# W960.net
KiCad netlist of a schematic drawn in EAGLE
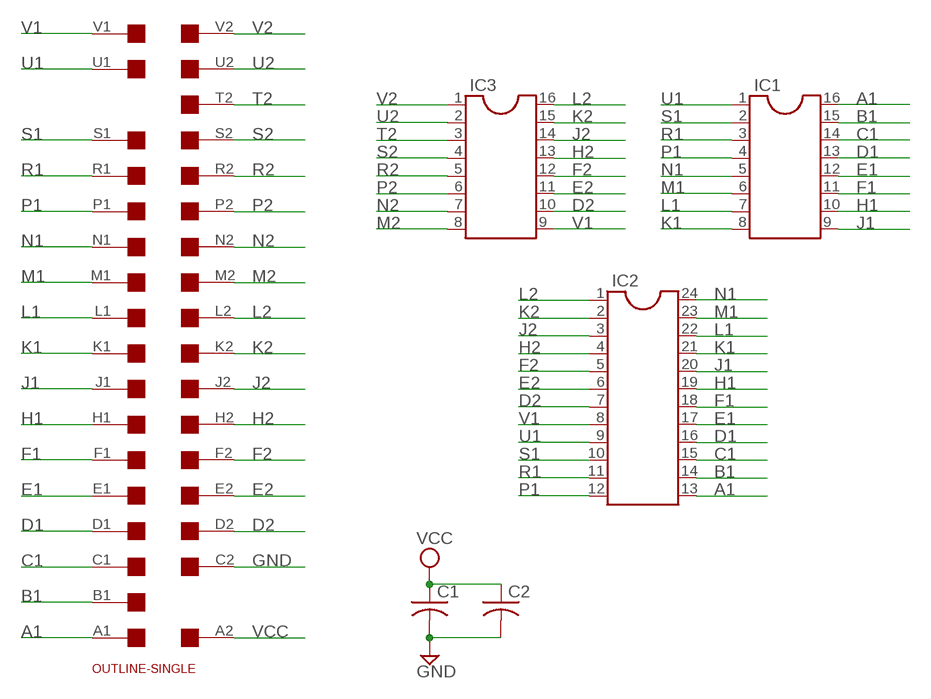
[diagram p0: schematic, sheet 1]

(export (version "E")
  (design (tool "Eeschema 10.0.6"))
  (components
    (comp (ref "C1")
      (value "C-US050-025X075")
      (footprint "eagle-import:C050-025X075")
      (libsource (lib "eagle-import") (part "C-US050-025X075"))
    )
    (comp (ref "C2")
      (value "C-US050-025X075")
      (footprint "eagle-import:C050-025X075")
      (libsource (lib "eagle-import") (part "C-US050-025X075"))
    )
    (comp (ref "IC1")
      (value "DIL16")
      (footprint "eagle-import:DIL16")
      (libsource (lib "eagle-import") (part "DIL16"))
    )
    (comp (ref "IC2")
      (value "DIL24-6")
      (footprint "eagle-import:DIL24-6")
      (libsource (lib "eagle-import") (part "DIL24-6"))
    )
    (comp (ref "IC3")
      (value "DIL16")
      (footprint "eagle-import:DIL16")
      (libsource (lib "eagle-import") (part "DIL16"))
    )
    (comp (ref "U$1")
      (value "EDGE-2CONNECTOR")
      (footprint "eagle-import:EDGE-CON2")
      (libsource (lib "eagle-import") (part "EDGE-2CONNECTOR"))
    )
    (comp (ref "U$2")
      (value "OUTLINE-SINGLE")
      (footprint "eagle-import:SINGLE")
      (libsource (lib "eagle-import") (part "OUTLINE-SINGLE"))
    )
  )
  (nets
    (net (code "1") (name "/A1") (class "Default")
      (node (ref "IC1") (pin "16") (pinfunction "16_16") (pintype "passive"))
      (node (ref "IC2") (pin "13") (pinfunction "13_13") (pintype "passive"))
      (node (ref "U$1") (pin "A1") (pinfunction "1_A1") (pintype "bidirectional"))
    )
    (net (code "2") (name "/B1") (class "Default")
      (node (ref "IC1") (pin "15") (pinfunction "15_15") (pintype "passive"))
      (node (ref "IC2") (pin "14") (pinfunction "14_14") (pintype "passive"))
      (node (ref "U$1") (pin "B1") (pinfunction "1_B1") (pintype "bidirectional"))
    )
    (net (code "3") (name "/C1") (class "Default")
      (node (ref "IC1") (pin "14") (pinfunction "14_14") (pintype "passive"))
      (node (ref "IC2") (pin "15") (pinfunction "15_15") (pintype "passive"))
      (node (ref "U$1") (pin "C1") (pinfunction "1_C1") (pintype "bidirectional"))
    )
    (net (code "4") (name "/D1") (class "Default")
      (node (ref "IC1") (pin "13") (pinfunction "13_13") (pintype "passive"))
      (node (ref "IC2") (pin "16") (pinfunction "16_16") (pintype "passive"))
      (node (ref "U$1") (pin "D1") (pinfunction "1_D1") (pintype "bidirectional"))
    )
    (net (code "5") (name "/D2") (class "Default")
      (node (ref "IC2") (pin "7") (pinfunction "7_7") (pintype "passive"))
      (node (ref "IC3") (pin "10") (pinfunction "10_10") (pintype "passive"))
      (node (ref "U$1") (pin "D2") (pinfunction "1_D2") (pintype "bidirectional"))
    )
    (net (code "6") (name "/E1") (class "Default")
      (node (ref "IC1") (pin "12") (pinfunction "12_12") (pintype "passive"))
      (node (ref "IC2") (pin "17") (pinfunction "17_17") (pintype "passive"))
      (node (ref "U$1") (pin "E1") (pinfunction "1_E1") (pintype "bidirectional"))
    )
    (net (code "7") (name "/E2") (class "Default")
      (node (ref "IC2") (pin "6") (pinfunction "6_6") (pintype "passive"))
      (node (ref "IC3") (pin "11") (pinfunction "11_11") (pintype "passive"))
      (node (ref "U$1") (pin "E2") (pinfunction "1_E2") (pintype "bidirectional"))
    )
    (net (code "8") (name "/F1") (class "Default")
      (node (ref "IC1") (pin "11") (pinfunction "11_11") (pintype "passive"))
      (node (ref "IC2") (pin "18") (pinfunction "18_18") (pintype "passive"))
      (node (ref "U$1") (pin "F1") (pinfunction "1_F1") (pintype "bidirectional"))
    )
    (net (code "9") (name "/F2") (class "Default")
      (node (ref "IC2") (pin "5") (pinfunction "5_5") (pintype "passive"))
      (node (ref "IC3") (pin "12") (pinfunction "12_12") (pintype "passive"))
      (node (ref "U$1") (pin "F2") (pinfunction "1_F2") (pintype "bidirectional"))
    )
    (net (code "10") (name "/H1") (class "Default")
      (node (ref "IC1") (pin "10") (pinfunction "10_10") (pintype "passive"))
      (node (ref "IC2") (pin "19") (pinfunction "19_19") (pintype "passive"))
      (node (ref "U$1") (pin "H1") (pinfunction "1_H1") (pintype "bidirectional"))
    )
    (net (code "11") (name "/H2") (class "Default")
      (node (ref "IC2") (pin "4") (pinfunction "4_4") (pintype "passive"))
      (node (ref "IC3") (pin "13") (pinfunction "13_13") (pintype "passive"))
      (node (ref "U$1") (pin "H2") (pinfunction "1_H2") (pintype "bidirectional"))
    )
    (net (code "12") (name "/J1") (class "Default")
      (node (ref "IC1") (pin "9") (pinfunction "9_9") (pintype "passive"))
      (node (ref "IC2") (pin "20") (pinfunction "20_20") (pintype "passive"))
      (node (ref "U$1") (pin "J1") (pinfunction "1_J1") (pintype "bidirectional"))
    )
    (net (code "13") (name "/J2") (class "Default")
      (node (ref "IC2") (pin "3") (pinfunction "3_3") (pintype "passive"))
      (node (ref "IC3") (pin "14") (pinfunction "14_14") (pintype "passive"))
      (node (ref "U$1") (pin "J2") (pinfunction "1_J2") (pintype "bidirectional"))
    )
    (net (code "14") (name "/K1") (class "Default")
      (node (ref "IC1") (pin "8") (pinfunction "8_8") (pintype "passive"))
      (node (ref "IC2") (pin "21") (pinfunction "21_21") (pintype "passive"))
      (node (ref "U$1") (pin "K1") (pinfunction "1_K1") (pintype "bidirectional"))
    )
    (net (code "15") (name "/K2") (class "Default")
      (node (ref "IC2") (pin "2") (pinfunction "2_2") (pintype "passive"))
      (node (ref "IC3") (pin "15") (pinfunction "15_15") (pintype "passive"))
      (node (ref "U$1") (pin "K2") (pinfunction "1_K2") (pintype "bidirectional"))
    )
    (net (code "16") (name "/L1") (class "Default")
      (node (ref "IC1") (pin "7") (pinfunction "7_7") (pintype "passive"))
      (node (ref "IC2") (pin "22") (pinfunction "22_22") (pintype "passive"))
      (node (ref "U$1") (pin "L1") (pinfunction "1_L1") (pintype "bidirectional"))
    )
    (net (code "17") (name "/L2") (class "Default")
      (node (ref "IC2") (pin "1") (pinfunction "1_1") (pintype "passive"))
      (node (ref "IC3") (pin "16") (pinfunction "16_16") (pintype "passive"))
      (node (ref "U$1") (pin "L2") (pinfunction "1_L2") (pintype "bidirectional"))
    )
    (net (code "18") (name "/M1") (class "Default")
      (node (ref "IC1") (pin "6") (pinfunction "6_6") (pintype "passive"))
      (node (ref "IC2") (pin "23") (pinfunction "23_23") (pintype "passive"))
      (node (ref "U$1") (pin "M1") (pinfunction "1_M1") (pintype "bidirectional"))
    )
    (net (code "19") (name "/M2") (class "Default")
      (node (ref "IC3") (pin "8") (pinfunction "8_8") (pintype "passive"))
      (node (ref "U$1") (pin "M2") (pinfunction "1_M2") (pintype "bidirectional"))
    )
    (net (code "20") (name "/N1") (class "Default")
      (node (ref "IC1") (pin "5") (pinfunction "5_5") (pintype "passive"))
      (node (ref "IC2") (pin "24") (pinfunction "24_24") (pintype "passive"))
      (node (ref "U$1") (pin "N1") (pinfunction "1_N1") (pintype "bidirectional"))
    )
    (net (code "21") (name "/N2") (class "Default")
      (node (ref "IC3") (pin "7") (pinfunction "7_7") (pintype "passive"))
      (node (ref "U$1") (pin "N2") (pinfunction "1_N2") (pintype "bidirectional"))
    )
    (net (code "22") (name "/P1") (class "Default")
      (node (ref "IC1") (pin "4") (pinfunction "4_4") (pintype "passive"))
      (node (ref "IC2") (pin "12") (pinfunction "12_12") (pintype "passive"))
      (node (ref "U$1") (pin "P1") (pinfunction "1_P1") (pintype "bidirectional"))
    )
    (net (code "23") (name "/P2") (class "Default")
      (node (ref "IC3") (pin "6") (pinfunction "6_6") (pintype "passive"))
      (node (ref "U$1") (pin "P2") (pinfunction "1_P2") (pintype "bidirectional"))
    )
    (net (code "24") (name "/R1") (class "Default")
      (node (ref "IC1") (pin "3") (pinfunction "3_3") (pintype "passive"))
      (node (ref "IC2") (pin "11") (pinfunction "11_11") (pintype "passive"))
      (node (ref "U$1") (pin "R1") (pinfunction "1_R1") (pintype "bidirectional"))
    )
    (net (code "25") (name "/R2") (class "Default")
      (node (ref "IC3") (pin "5") (pinfunction "5_5") (pintype "passive"))
      (node (ref "U$1") (pin "R2") (pinfunction "1_R2") (pintype "bidirectional"))
    )
    (net (code "26") (name "/S1") (class "Default")
      (node (ref "IC1") (pin "2") (pinfunction "2_2") (pintype "passive"))
      (node (ref "IC2") (pin "10") (pinfunction "10_10") (pintype "passive"))
      (node (ref "U$1") (pin "S1") (pinfunction "1_S1") (pintype "bidirectional"))
    )
    (net (code "27") (name "/S2") (class "Default")
      (node (ref "IC3") (pin "4") (pinfunction "4_4") (pintype "passive"))
      (node (ref "U$1") (pin "S2") (pinfunction "1_S2") (pintype "bidirectional"))
    )
    (net (code "28") (name "/T2") (class "Default")
      (node (ref "IC3") (pin "3") (pinfunction "3_3") (pintype "passive"))
      (node (ref "U$1") (pin "T2") (pinfunction "1_T2") (pintype "bidirectional"))
    )
    (net (code "29") (name "/U1") (class "Default")
      (node (ref "IC1") (pin "1") (pinfunction "1_1") (pintype "passive"))
      (node (ref "IC2") (pin "9") (pinfunction "9_9") (pintype "passive"))
      (node (ref "U$1") (pin "U1") (pinfunction "1_U1") (pintype "bidirectional"))
    )
    (net (code "30") (name "/U2") (class "Default")
      (node (ref "IC3") (pin "2") (pinfunction "2_2") (pintype "passive"))
      (node (ref "U$1") (pin "U2") (pinfunction "1_U2") (pintype "bidirectional"))
    )
    (net (code "31") (name "/V1") (class "Default")
      (node (ref "IC2") (pin "8") (pinfunction "8_8") (pintype "passive"))
      (node (ref "IC3") (pin "9") (pinfunction "9_9") (pintype "passive"))
      (node (ref "U$1") (pin "V1") (pinfunction "1_V1") (pintype "bidirectional"))
    )
    (net (code "32") (name "/V2") (class "Default")
      (node (ref "IC3") (pin "1") (pinfunction "1_1") (pintype "passive"))
      (node (ref "U$1") (pin "V2") (pinfunction "1_V2") (pintype "bidirectional"))
    )
    (net (code "33") (name "GND") (class "Default")
      (node (ref "C1") (pin "2") (pinfunction "2_2") (pintype "passive"))
      (node (ref "C2") (pin "2") (pinfunction "2_2") (pintype "passive"))
      (node (ref "U$1") (pin "C2") (pinfunction "1_C2") (pintype "bidirectional"))
    )
    (net (code "34") (name "VCC") (class "Default")
      (node (ref "C1") (pin "1") (pinfunction "1_1") (pintype "passive"))
      (node (ref "C2") (pin "1") (pinfunction "1_1") (pintype "passive"))
      (node (ref "U$1") (pin "A2") (pinfunction "1_A2") (pintype "bidirectional"))
    )
  )
)
